# schematic.net
KiCad netlist of a schematic drawn in Altium Designer
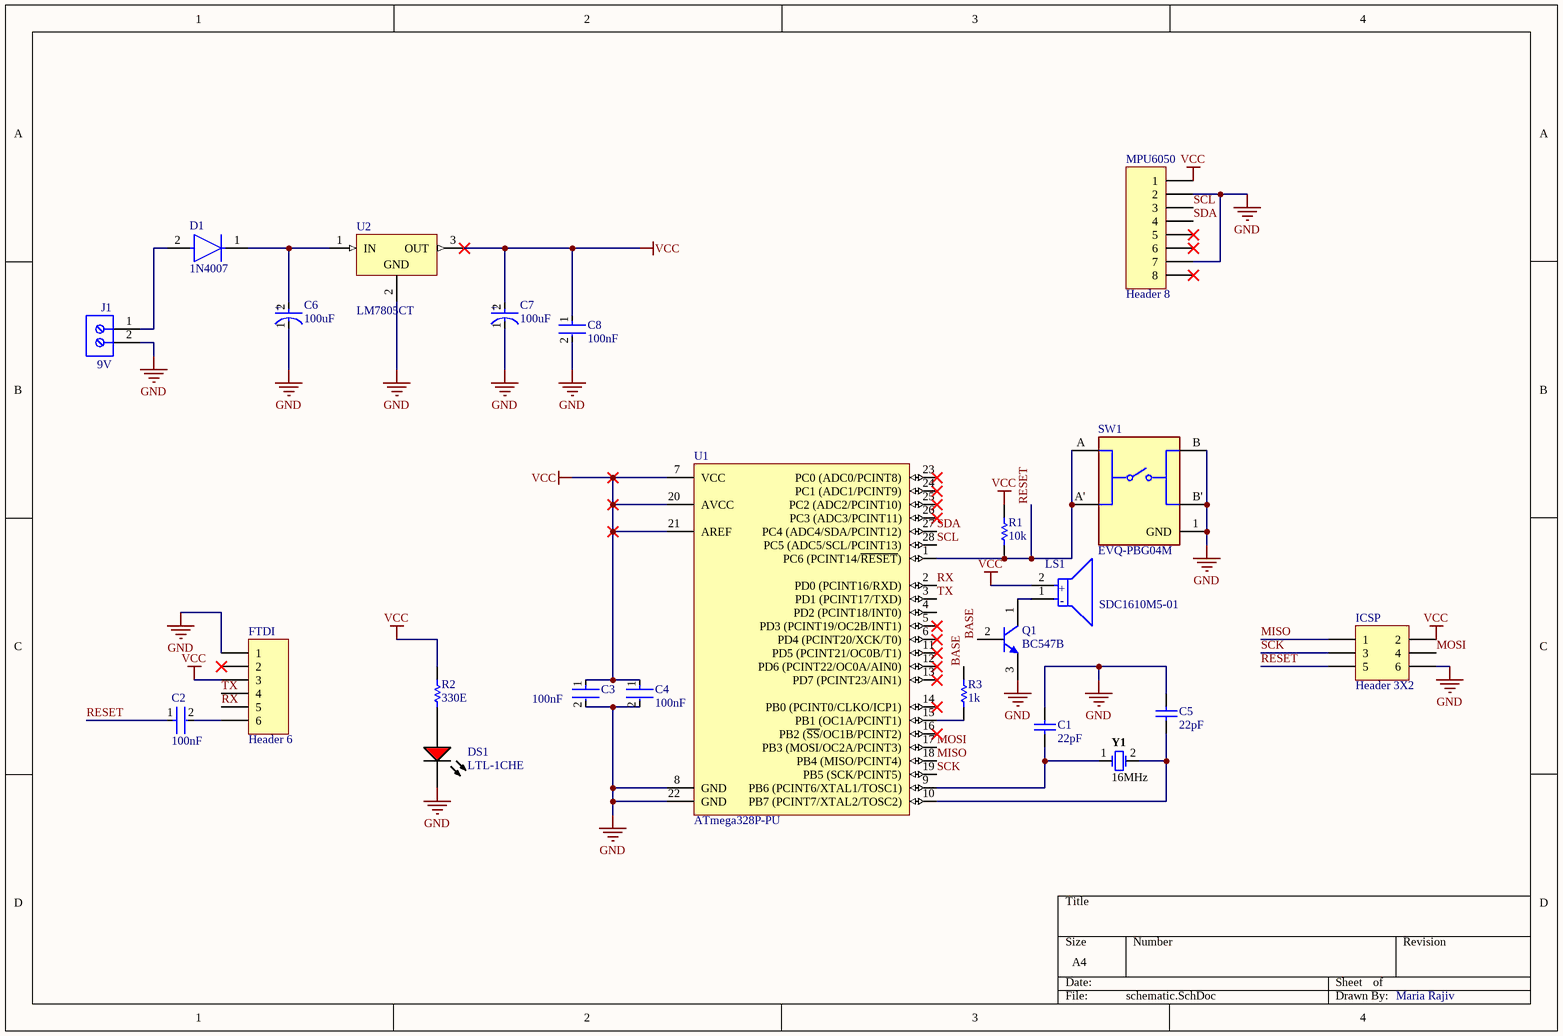
[diagram p0: schematic.SchDoc]

(export (version "E")
  (design (tool "Eeschema 10.0.6"))
  (components
    (comp (ref "C1")
      (value "22pF")
      (footprint "KEMT-C315-THT-2")
      (description "Capacitor, Ceramic, 22 pF, +/-10 %, 100 V, -55 to 125 degC, 2-Pin THD, RoHS, Bulk")
      (libsource (lib "Altium Content Vault") (part "CAP-NP-2"))
    )
    (comp (ref "C2")
      (value "100nF")
      (footprint "FP-RCE1A2-MFG")
      (description "Cap Ceramic 100nF 100V X7R ±10% Radial 2.5mm +125°C Automotive Ammo Pack")
      (fields (field (name "TOLERANCE") "10%"))
      (libsource (lib "Altium Content Vault") (part "02cd4be3c70576c341d710602a673aa"))
    )
    (comp (ref "C3")
      (value "100nF")
      (footprint "FP-RCE1K1-2_5-MFG")
      (description "Cap Ceramic Monolithic 100nF 100V 10% Thru-Hole Bulk")
      (fields (field (name "TOLERANCE") "10%"))
      (libsource (lib "Altium Content Vault") (part "02cd4be3c70576c341d710602a673aa"))
    )
    (comp (ref "C4")
      (value "100nF")
      (footprint "FP-RCE1K1-2_5-MFG")
      (description "Cap Ceramic Monolithic 100nF 100V 10% Thru-Hole Bulk")
      (fields (field (name "TOLERANCE") "10%"))
      (libsource (lib "Altium Content Vault") (part "02cd4be3c70576c341d710602a673aa"))
    )
    (comp (ref "C5")
      (value "22pF")
      (footprint "KEMT-C315-THT-2")
      (description "Capacitor, Ceramic, 22 pF, +/-10 %, 100 V, -55 to 125 degC, 2-Pin THD, RoHS, Bulk")
      (libsource (lib "Altium Content Vault") (part "CAP-NP-2"))
    )
    (comp (ref "C6")
      (value "100uF")
      (footprint "FP-RAD-TH-D_6_3_0_5-L_11-MFG")
      (description "Aluminum Electrolytic Capacitors (Radial Lead Type) 2.2uF ±20% 250V")
      (fields (field (name "TOLERANCE") "20%"))
      (libsource (lib "Altium Content Vault") (part "203bc49f2ac43e59fd269a8c329ed05"))
    )
    (comp (ref "C7")
      (value "100uF")
      (footprint "FP-RAD-TH-D_6_3_0_5-L_11-MFG")
      (description "Aluminum Electrolytic Capacitors (Radial Lead Type) 2.2uF ±20% 250V")
      (fields (field (name "TOLERANCE") "20%"))
      (libsource (lib "Altium Content Vault") (part "203bc49f2ac43e59fd269a8c329ed05"))
    )
    (comp (ref "C8")
      (value "100nF")
      (footprint "FP-RCE1K1-2_5-MFG")
      (description "Cap Ceramic Monolithic 100nF 100V 10% Thru-Hole Bulk")
      (fields (field (name "TOLERANCE") "10%"))
      (libsource (lib "Altium Content Vault") (part "02cd4be3c70576c341d710602a673aa"))
    )
    (comp (ref "D1")
      (value "1N4007")
      (footprint "FP-1N4007E-E3-54-MFG")
      (description "DIODE GEN PURP 1KV 1A DO204AL")
      (libsource (lib "Altium Content Vault") (part "d7152d700b627762746794eb795d46e"))
    )
    (comp (ref "DS1")
      (value "LTL-1CHE")
      (footprint "INDPR60-254-520X380X650")
      (description "Radial LED, 12.6 mcd, 20 mA, 2 V, -55 to 100 degC, 2-Pin THD, RoHS, Bulk")
      (fields (field (name "TOLERANCE") "20%"))
      (libsource (lib "Altium Content Vault") (part "LED-RED-AK-2"))
    )
    (comp (ref "FTDI")
      (value "Header 6")
      (footprint "HDR1X6")
      (description "Header, 6-Pin")
      (fields (field (name "PUBLISHER") "Altium Limited"))
      (libsource (lib "Miscellaneous Connectors") (part "Header 6"))
    )
    (comp (ref "ICSP")
      (value "Header 3X2")
      (footprint "HDR2X3")
      (description "Header, 3-Pin, Dual row")
      (fields (field (name "PUBLISHER") "Altium Limited"))
      (libsource (lib "Miscellaneous Connectors") (part "Header 3X2"))
    )
    (comp (ref "J1")
      (value "9V")
      (footprint "691211720002")
      (description "211 Series 5MM Pitch Straight, Pcb Terminal Block, Through Hole, 2 Way")
      (fields (field (name "VOLTAGE") "300V"))
      (libsource (lib "Altium Content Vault") (part "TBL - 1R - 02P - Screw"))
    )
    (comp (ref "LS1")
      (value "SDC1610M5-01")
      (footprint "FP-SDC1610M5-01-MFG")
      (description "AUDIO MAGNETIC INDICATOR 4-8V TH")
      (libsource (lib "Altium Content Vault") (part "f7ec632b6fea80cbef86dc3340f200c"))
    )
    (comp (ref "MPU6050")
      (value "Header 8")
      (footprint "HDR1X8")
      (description "Header, 8-Pin")
      (fields (field (name "PUBLISHER") "Altium Limited"))
      (libsource (lib "Miscellaneous Connectors") (part "Header 8"))
    )
    (comp (ref "Q1")
      (value "BC547B")
      (footprint "ONSC-TO-92-3-29-11")
      (description "Amplifier Transistor, NPN Silicon, 3-Pin TO-92, Bulk Box")
      (fields (field (name "MANUFACTURER") "On Semiconductor"))
      (libsource (lib "Altium Content Vault") (part "ONSC-NPN-C1B2E3-3"))
    )
    (comp (ref "R1")
      (value "10k")
      (footprint "AXIAL-0.3")
      (description "Resistor")
      (fields (field (name "PUBLISHER") "Altium Limited"))
      (libsource (lib "Miscellaneous Devices") (part "Res1"))
    )
    (comp (ref "R2")
      (value "330E")
      (footprint "AXIAL-0.3")
      (description "Resistor")
      (fields (field (name "PUBLISHER") "Altium Limited"))
      (libsource (lib "Miscellaneous Devices") (part "Res1"))
    )
    (comp (ref "R3")
      (value "1k")
      (footprint "AXIAL-0.3")
      (description "Resistor")
      (fields (field (name "PUBLISHER") "Altium Limited"))
      (libsource (lib "Miscellaneous Devices") (part "Res1"))
    )
    (comp (ref "SW1")
      (value "EVQ-PBG04M")
      (footprint "FP-EVQ-PBG04M-MFG")
      (description "SWITCH TACTILE SPST-NO 0.02A 15V")
      (libsource (lib "Altium Content Vault") (part "2124b69ba03152b6ee5348f5a6e82e9"))
    )
    (comp (ref "U1")
      (value "ATmega328P-PU")
      (footprint "28P3")
      (libsource (lib "Altium Content Vault") (part "MC-8B-ATM48-IL28"))
    )
    (comp (ref "U2")
      (value "LM7805CT")
      (footprint "FAIR-TO-220-3")
      (description "Positive Voltage Regulator, 5 V, 1 A, -40 to 125 degC, 3-Pin TO-220, RoHS, Tube")
      (fields (field (name "MANUFACTURER") "FairchildSemiconductor"))
      (libsource (lib "Altium Content Vault") (part "FAIR-LM7805CT-TO220-3"))
    )
    (comp (ref "Y1")
      (value "16MHz")
      (footprint "FOX-FOXSLF160-20")
      (description "Resistance Weld Thru-Hole Crystal, 16 MHz, -20 to 70 degC, 2-Pin THD, RoHS, Bulk")
      (fields (field (name "TOLERANCE") "1%"))
      (libsource (lib "Altium Content Vault") (part "XTAL-1-2-2"))
    )
  )
  (nets
    (net (code "1") (name "/BASE") (class "Default")
      (node (ref "Q1") (pin "2") (pinfunction "B_2") (pintype "passive"))
      (node (ref "R3") (pin "2") (pinfunction "2_2") (pintype "passive"))
    )
    (net (code "2") (name "/MISO") (class "Default")
      (node (ref "ICSP") (pin "1") (pinfunction "1_1") (pintype "passive"))
      (node (ref "U1") (pin "18") (pinfunction "PB4_(MISO/PCINT4)_18") (pintype "bidirectional"))
    )
    (net (code "3") (name "/MOSI") (class "Default")
      (node (ref "ICSP") (pin "4") (pinfunction "4_4") (pintype "passive"))
      (node (ref "U1") (pin "17") (pinfunction "PB3_(MOSI/OC2A/PCINT3)_17") (pintype "bidirectional"))
    )
    (net (code "4") (name "/RESET") (class "Default")
      (node (ref "C2") (pin "1") (pinfunction "1_1") (pintype "passive"))
      (node (ref "ICSP") (pin "5") (pinfunction "5_5") (pintype "passive"))
      (node (ref "R1") (pin "1") (pinfunction "1_1") (pintype "passive"))
      (node (ref "SW1") (pin "A") (pinfunction "A_A") (pintype "passive"))
      (node (ref "SW1") (pin "A'") (pinfunction "A'_A'") (pintype "passive"))
      (node (ref "U1") (pin "1") (pinfunction "PC6_(PCINT14/~{RESET})_1") (pintype "bidirectional"))
    )
    (net (code "5") (name "/RX") (class "Default")
      (node (ref "FTDI") (pin "5") (pinfunction "5_5") (pintype "passive"))
      (node (ref "U1") (pin "2") (pinfunction "PD0_(PCINT16/RXD)_2") (pintype "bidirectional"))
    )
    (net (code "6") (name "/SCK") (class "Default")
      (node (ref "ICSP") (pin "3") (pinfunction "3_3") (pintype "passive"))
      (node (ref "U1") (pin "19") (pinfunction "PB5_(SCK/PCINT5)_19") (pintype "bidirectional"))
    )
    (net (code "7") (name "/SCL") (class "Default")
      (node (ref "MPU6050") (pin "3") (pinfunction "3_3") (pintype "passive"))
      (node (ref "U1") (pin "28") (pinfunction "PC5_(ADC5/SCL/PCINT13)_28") (pintype "bidirectional"))
    )
    (net (code "8") (name "/SDA") (class "Default")
      (node (ref "MPU6050") (pin "4") (pinfunction "4_4") (pintype "passive"))
      (node (ref "U1") (pin "27") (pinfunction "PC4_(ADC4/SDA/PCINT12)_27") (pintype "bidirectional"))
    )
    (net (code "9") (name "/TX") (class "Default")
      (node (ref "FTDI") (pin "4") (pinfunction "4_4") (pintype "passive"))
      (node (ref "U1") (pin "3") (pinfunction "PD1_(PCINT17/TXD)_3") (pintype "bidirectional"))
    )
    (net (code "10") (name "GND") (class "Default")
      (node (ref "C1") (pin "2") (pinfunction "2_2") (pintype "passive"))
      (node (ref "C3") (pin "2") (pinfunction "2_2") (pintype "passive"))
      (node (ref "C4") (pin "2") (pinfunction "2_2") (pintype "passive"))
      (node (ref "C5") (pin "2") (pinfunction "2_2") (pintype "passive"))
      (node (ref "C6") (pin "1") (pinfunction "C_1") (pintype "passive"))
      (node (ref "C7") (pin "1") (pinfunction "C_1") (pintype "passive"))
      (node (ref "C8") (pin "2") (pinfunction "2_2") (pintype "passive"))
      (node (ref "DS1") (pin "2") (pinfunction "K_2") (pintype "passive"))
      (node (ref "FTDI") (pin "1") (pinfunction "1_1") (pintype "passive"))
      (node (ref "ICSP") (pin "6") (pinfunction "6_6") (pintype "passive"))
      (node (ref "J1") (pin "2") (pinfunction "2_2") (pintype "passive"))
      (node (ref "MPU6050") (pin "2") (pinfunction "2_2") (pintype "passive"))
      (node (ref "MPU6050") (pin "7") (pinfunction "7_7") (pintype "passive"))
      (node (ref "Q1") (pin "3") (pinfunction "E_3") (pintype "passive"))
      (node (ref "SW1") (pin "1") (pinfunction "GND_1") (pintype "power_in"))
      (node (ref "SW1") (pin "B") (pinfunction "B_B") (pintype "passive"))
      (node (ref "SW1") (pin "B'") (pinfunction "B'_B'") (pintype "passive"))
      (node (ref "U1") (pin "22") (pinfunction "GND_22") (pintype "power_in"))
      (node (ref "U1") (pin "8") (pinfunction "GND_8") (pintype "power_in"))
      (node (ref "U2") (pin "2") (pinfunction "GND_2") (pintype "power_in"))
    )
    (net (code "11") (name "Net-(C2-Pad2)") (class "Default")
      (node (ref "C2") (pin "2") (pinfunction "2_2") (pintype "passive"))
      (node (ref "FTDI") (pin "6") (pinfunction "6_6") (pintype "passive"))
    )
    (net (code "12") (name "Net-(C6-A)") (class "Default")
      (node (ref "C6") (pin "2") (pinfunction "A_2") (pintype "passive"))
      (node (ref "D1") (pin "1") (pinfunction "C_1") (pintype "passive"))
      (node (ref "U2") (pin "1") (pinfunction "IN_1") (pintype "input"))
    )
    (net (code "13") (name "Net-(D1-A)") (class "Default")
      (node (ref "D1") (pin "2") (pinfunction "A_2") (pintype "passive"))
      (node (ref "J1") (pin "1") (pinfunction "1_1") (pintype "passive"))
    )
    (net (code "14") (name "Net-(DS1-A)") (class "Default")
      (node (ref "DS1") (pin "1") (pinfunction "A_1") (pintype "passive"))
      (node (ref "R2") (pin "1") (pinfunction "1_1") (pintype "passive"))
    )
    (net (code "15") (name "Net-(LS1-C)") (class "Default")
      (node (ref "LS1") (pin "1") (pinfunction "C_1") (pintype "passive"))
      (node (ref "Q1") (pin "1") (pinfunction "C_1") (pintype "passive"))
    )
    (net (code "16") (name "Net-(U1-PB1_(OC1A{slash}PCINT1))") (class "Default")
      (node (ref "R3") (pin "1") (pinfunction "1_1") (pintype "passive"))
      (node (ref "U1") (pin "15") (pinfunction "PB1_(OC1A/PCINT1)_15") (pintype "bidirectional"))
    )
    (net (code "17") (name "Net-(U1-PB6_(PCINT6{slash}XTAL1{slash}TOSC1))") (class "Default")
      (node (ref "C1") (pin "1") (pinfunction "1_1") (pintype "passive"))
      (node (ref "U1") (pin "9") (pinfunction "PB6_(PCINT6/XTAL1/TOSC1)_9") (pintype "bidirectional"))
      (node (ref "Y1") (pin "1") (pinfunction "1_1") (pintype "passive"))
    )
    (net (code "18") (name "Net-(U1-PB7_(PCINT7{slash}XTAL2{slash}TOSC2))") (class "Default")
      (node (ref "C5") (pin "1") (pinfunction "1_1") (pintype "passive"))
      (node (ref "U1") (pin "10") (pinfunction "PB7_(PCINT7/XTAL2/TOSC2)_10") (pintype "bidirectional"))
      (node (ref "Y1") (pin "2") (pinfunction "2_2") (pintype "passive"))
    )
    (net (code "19") (name "VCC") (class "Default")
      (node (ref "C3") (pin "1") (pinfunction "1_1") (pintype "passive"))
      (node (ref "C4") (pin "1") (pinfunction "1_1") (pintype "passive"))
      (node (ref "C7") (pin "2") (pinfunction "A_2") (pintype "passive"))
      (node (ref "C8") (pin "1") (pinfunction "1_1") (pintype "passive"))
      (node (ref "FTDI") (pin "3") (pinfunction "3_3") (pintype "passive"))
      (node (ref "ICSP") (pin "2") (pinfunction "2_2") (pintype "passive"))
      (node (ref "LS1") (pin "2") (pinfunction "A_2") (pintype "passive"))
      (node (ref "MPU6050") (pin "1") (pinfunction "1_1") (pintype "passive"))
      (node (ref "R1") (pin "2") (pinfunction "2_2") (pintype "passive"))
      (node (ref "R2") (pin "2") (pinfunction "2_2") (pintype "passive"))
      (node (ref "U1") (pin "20") (pinfunction "AVCC_20") (pintype "power_in"))
      (node (ref "U1") (pin "21") (pinfunction "AREF_21") (pintype "power_in"))
      (node (ref "U1") (pin "7") (pinfunction "VCC_7") (pintype "power_in"))
      (node (ref "U2") (pin "3") (pinfunction "OUT_3") (pintype "output"))
    )
    (net (code "20") (name "unconnected-(FTDI-Pad2)") (class "Default")
      (node (ref "FTDI") (pin "2") (pinfunction "2_2") (pintype "passive+no_connect"))
    )
    (net (code "21") (name "unconnected-(MPU6050-Pad5)") (class "Default")
      (node (ref "MPU6050") (pin "5") (pinfunction "5_5") (pintype "passive+no_connect"))
    )
    (net (code "22") (name "unconnected-(MPU6050-Pad6)") (class "Default")
      (node (ref "MPU6050") (pin "6") (pinfunction "6_6") (pintype "passive+no_connect"))
    )
    (net (code "23") (name "unconnected-(MPU6050-Pad8)") (class "Default")
      (node (ref "MPU6050") (pin "8") (pinfunction "8_8") (pintype "passive+no_connect"))
    )
    (net (code "24") (name "unconnected-(U1-PB0_(PCINT0{slash}CLKO{slash}ICP1)-Pad14)") (class "Default")
      (node (ref "U1") (pin "14") (pinfunction "PB0_(PCINT0/CLKO/ICP1)_14") (pintype "bidirectional+no_connect"))
    )
    (net (code "25") (name "unconnected-(U1-PB2_(~{SS}{slash}OC1B{slash}PCINT2)-Pad16)") (class "Default")
      (node (ref "U1") (pin "16") (pinfunction "PB2_(~{SS}/OC1B/PCINT2)_16") (pintype "bidirectional+no_connect"))
    )
    (net (code "26") (name "unconnected-(U1-PC0_(ADC0{slash}PCINT8)-Pad23)") (class "Default")
      (node (ref "U1") (pin "23") (pinfunction "PC0_(ADC0/PCINT8)_23") (pintype "bidirectional+no_connect"))
    )
    (net (code "27") (name "unconnected-(U1-PC1_(ADC1{slash}PCINT9)-Pad24)") (class "Default")
      (node (ref "U1") (pin "24") (pinfunction "PC1_(ADC1/PCINT9)_24") (pintype "bidirectional+no_connect"))
    )
    (net (code "28") (name "unconnected-(U1-PC2_(ADC2{slash}PCINT10)-Pad25)") (class "Default")
      (node (ref "U1") (pin "25") (pinfunction "PC2_(ADC2/PCINT10)_25") (pintype "bidirectional+no_connect"))
    )
    (net (code "29") (name "unconnected-(U1-PC3_(ADC3{slash}PCINT11)-Pad26)") (class "Default")
      (node (ref "U1") (pin "26") (pinfunction "PC3_(ADC3/PCINT11)_26") (pintype "bidirectional+no_connect"))
    )
    (net (code "30") (name "unconnected-(U1-PD2_(PCINT18{slash}INT0)-Pad4)") (class "Default")
      (node (ref "U1") (pin "4") (pinfunction "PD2_(PCINT18/INT0)_4") (pintype "bidirectional"))
    )
    (net (code "31") (name "unconnected-(U1-PD3_(PCINT19{slash}OC2B{slash}INT1)-Pad5)") (class "Default")
      (node (ref "U1") (pin "5") (pinfunction "PD3_(PCINT19/OC2B/INT1)_5") (pintype "bidirectional+no_connect"))
    )
    (net (code "32") (name "unconnected-(U1-PD4_(PCINT20{slash}XCK{slash}T0)-Pad6)") (class "Default")
      (node (ref "U1") (pin "6") (pinfunction "PD4_(PCINT20/XCK/T0)_6") (pintype "bidirectional+no_connect"))
    )
    (net (code "33") (name "unconnected-(U1-PD5_(PCINT21{slash}OC0B{slash}T1)-Pad11)") (class "Default")
      (node (ref "U1") (pin "11") (pinfunction "PD5_(PCINT21/OC0B/T1)_11") (pintype "bidirectional+no_connect"))
    )
    (net (code "34") (name "unconnected-(U1-PD6_(PCINT22{slash}OC0A{slash}AIN0)-Pad12)") (class "Default")
      (node (ref "U1") (pin "12") (pinfunction "PD6_(PCINT22/OC0A/AIN0)_12") (pintype "bidirectional+no_connect"))
    )
    (net (code "35") (name "unconnected-(U1-PD7_(PCINT23{slash}AIN1)-Pad13)") (class "Default")
      (node (ref "U1") (pin "13") (pinfunction "PD7_(PCINT23/AIN1)_13") (pintype "bidirectional+no_connect"))
    )
  )
)
